# 2018-12-17_02-16-071.net
KiCad netlist of a schematic drawn in Altium Designer
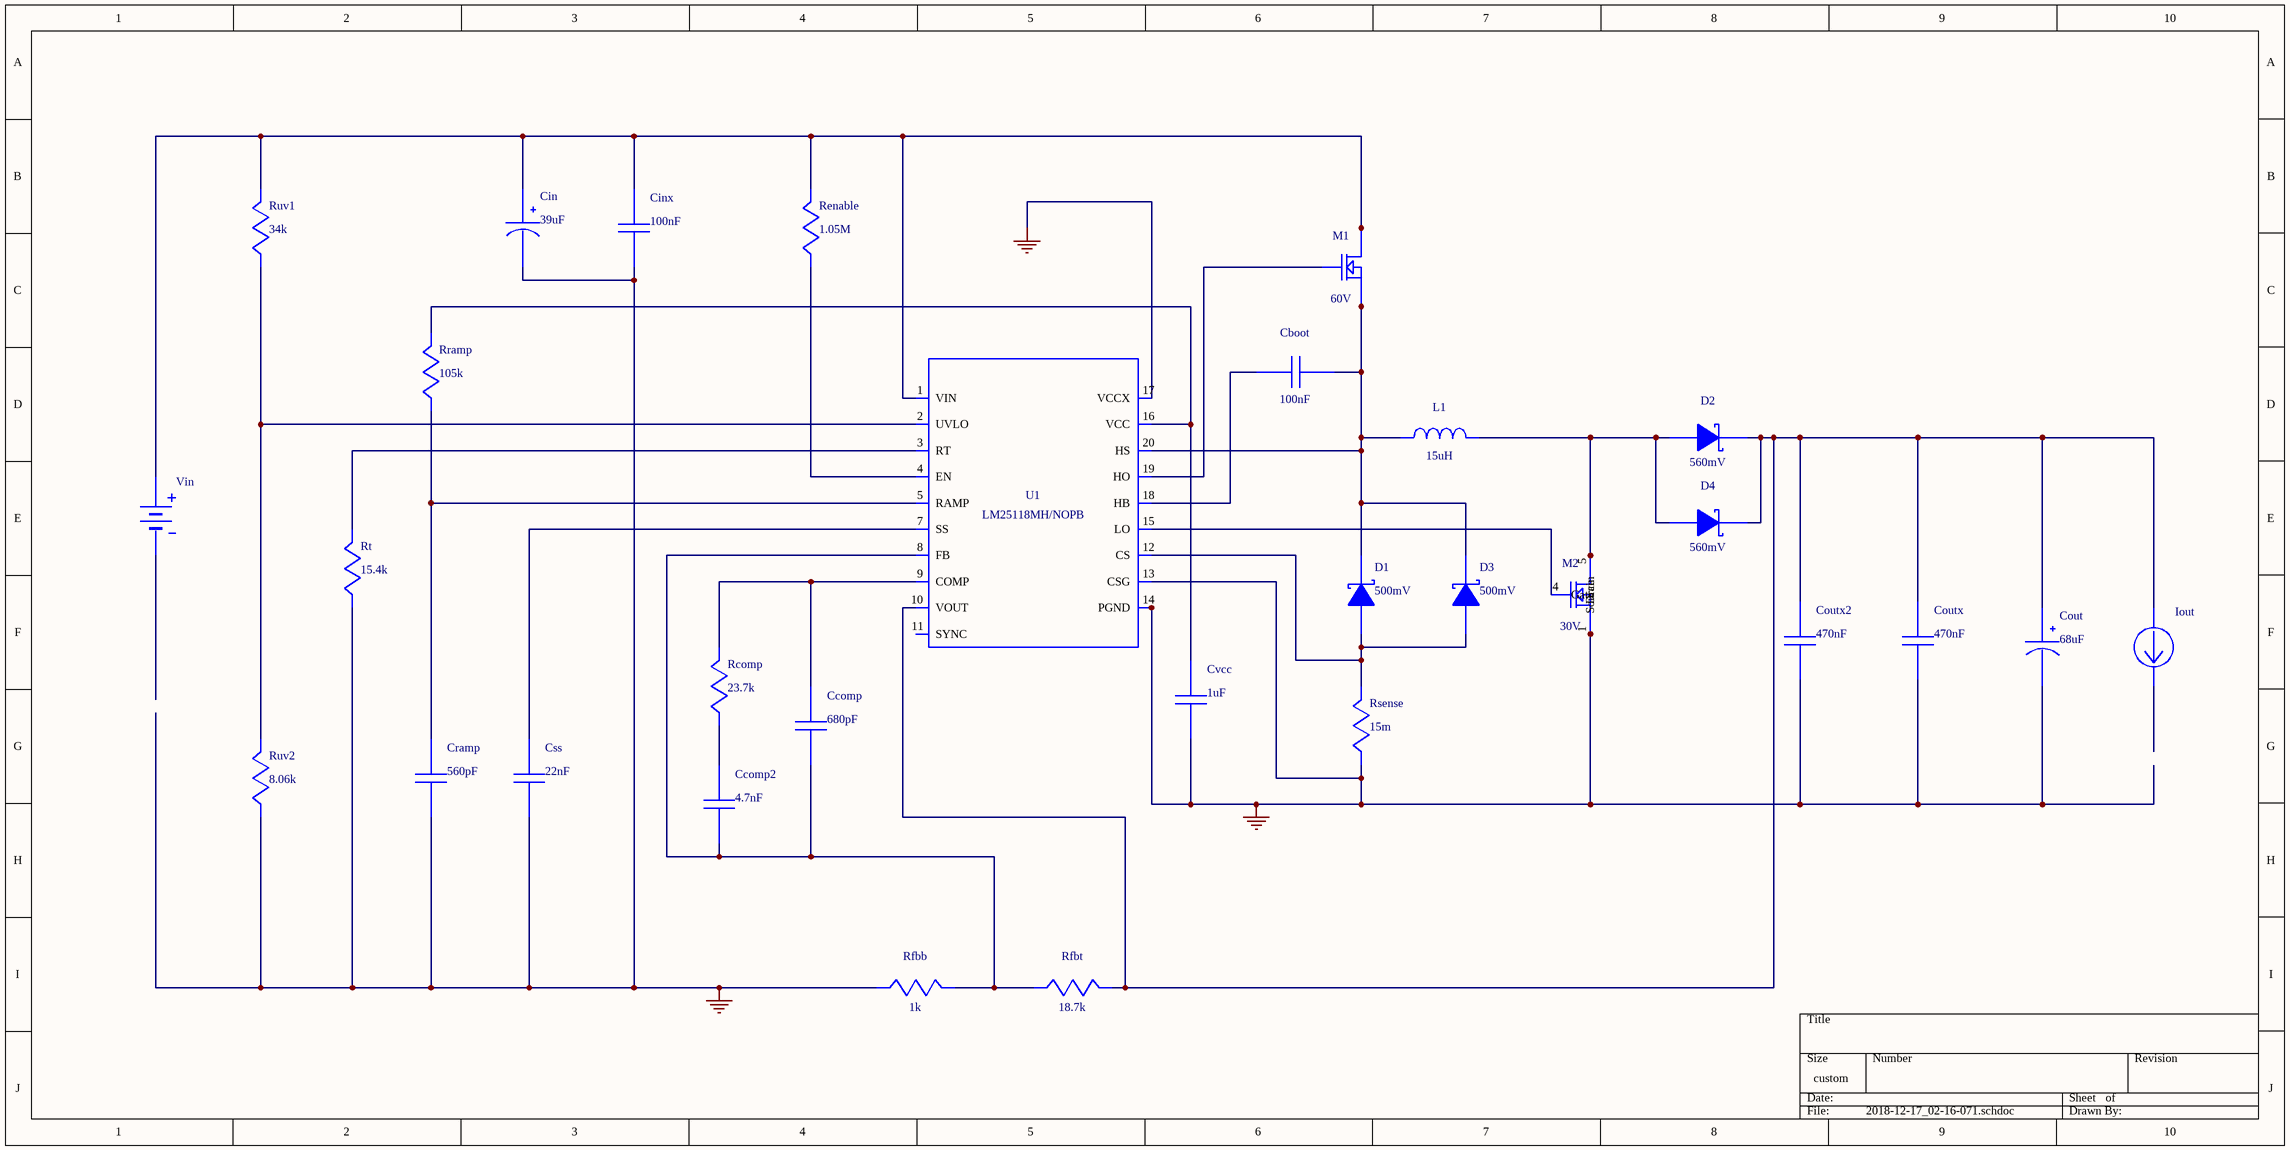
[diagram p0: 2018-12-17_02-16-071.schdoc]

(export (version "E")
  (design (tool "Eeschema 10.0.6"))
  (components
    (comp (ref "Cboot")
      (value "100nF")
      (description "08053C104JAZ2A")
      (libsource (lib "TI WEBENCH") (part "Cboot"))
    )
    (comp (ref "Ccomp")
      (value "680pF")
      (description "CGA2B2C0G1H681J0")
      (fields (field (name "MANUFACTURER PART NUMBER") "CGA2B2C0G1H681J050BA"))
      (libsource (lib "TI WEBENCH") (part "Ccomp"))
    )
    (comp (ref "Ccomp2")
      (value "4.7nF")
      (description "CGA4C2C0G1H472J0")
      (fields (field (name "MANUFACTURER PART NUMBER") "CGA4C2C0G1H472J060AA"))
      (libsource (lib "TI WEBENCH") (part "Ccomp2"))
    )
    (comp (ref "Cin") (value "39uF") (description "50SVPF39M") (libsource (lib "TI WEBENCH") (part "Cin")))
    (comp (ref "Cinx")
      (value "100nF")
      (description "C1005X7R1H104K05")
      (fields (field (name "MANUFACTURER PART NUMBER") "C1005X7R1H104K050BB"))
      (libsource (lib "TI WEBENCH") (part "Cinx"))
    )
    (comp (ref "Cout") (value "68uF") (description "50SVPF68M") (libsource (lib "TI WEBENCH") (part "Cout")))
    (comp (ref "Coutx")
      (value "470nF")
      (description "C1608X7R1H474K08")
      (fields (field (name "MANUFACTURER PART NUMBER") "C1608X7R1H474K080AC"))
      (libsource (lib "TI WEBENCH") (part "Coutx"))
    )
    (comp (ref "Coutx2")
      (value "470nF")
      (description "C1608X7R1H474K08")
      (fields (field (name "MANUFACTURER PART NUMBER") "C1608X7R1H474K080AC"))
      (libsource (lib "TI WEBENCH") (part "Coutx2"))
    )
    (comp (ref "Cramp")
      (value "560pF")
      (description "GRM1555C1H561JA0")
      (fields (field (name "MANUFACTURER PART NUMBER") "GRM1555C1H561JA01J"))
      (libsource (lib "TI WEBENCH") (part "Cramp"))
    )
    (comp (ref "Css")
      (value "22nF")
      (description "CGA4J2C0G1H223J1")
      (fields (field (name "MANUFACTURER PART NUMBER") "CGA4J2C0G1H223J125AA"))
      (libsource (lib "TI WEBENCH") (part "Css"))
    )
    (comp (ref "Cvcc")
      (value "1uF")
      (description "C1608X5R1H105K08")
      (fields (field (name "MANUFACTURER PART NUMBER") "C1608X5R1H105K080AB"))
      (libsource (lib "TI WEBENCH") (part "Cvcc"))
    )
    (comp (ref "D1") (value "500mV") (description "B340A-13-F") (libsource (lib "TI WEBENCH") (part "D1")))
    (comp (ref "D2") (value "560mV") (description "PDS760-13") (libsource (lib "TI WEBENCH") (part "D2")))
    (comp (ref "D3") (value "500mV") (description "B340A-13-F") (libsource (lib "TI WEBENCH") (part "D3")))
    (comp (ref "D4") (value "560mV") (description "PDS760-13") (libsource (lib "TI WEBENCH") (part "D4")))
    (comp (ref "Iout") (value "WB_CURRENT_LOAD") (libsource (lib "TI WEBENCH") (part "Iout")))
    (comp (ref "L1") (value "15uH") (description "XAL1010-153MEB") (libsource (lib "TI WEBENCH") (part "L1")))
    (comp (ref "M1") (value "60V") (description "BSZ100N06LS3 G") (libsource (lib "TI WEBENCH") (part "M1")))
    (comp (ref "M2") (value "30V") (description "CSD17308Q3") (libsource (lib "TI WEBENCH") (part "M2")))
    (comp (ref "Rcomp")
      (value "23.7k")
      (description "RC0201FR-0723K7L")
      (libsource (lib "TI WEBENCH") (part "Rcomp"))
    )
    (comp (ref "Renable")
      (value "1.05M")
      (description "CRCW04021M05FKED")
      (libsource (lib "TI WEBENCH") (part "Renable"))
    )
    (comp (ref "Rfbb")
      (value "1k")
      (description "ERJ-6ENF1001V")
      (libsource (lib "TI WEBENCH") (part "Rfbb"))
    )
    (comp (ref "Rfbt")
      (value "18.7k")
      (description "RC0201FR-0718K7L")
      (libsource (lib "TI WEBENCH") (part "Rfbt"))
    )
    (comp (ref "Rramp")
      (value "105k")
      (description "RC0201FR-07105KL")
      (libsource (lib "TI WEBENCH") (part "Rramp"))
    )
    (comp (ref "Rsense")
      (value "15m")
      (description "PRL1632-R015-F-T")
      (fields (field (name "MANUFACTURER PART NUMBER") "PRL1632-R015-F-T1"))
      (libsource (lib "TI WEBENCH") (part "Rsense"))
    )
    (comp (ref "Rt")
      (value "15.4k")
      (description "RC0201FR-0715K4L")
      (libsource (lib "TI WEBENCH") (part "Rt"))
    )
    (comp (ref "Ruv1")
      (value "34k")
      (description "CRCW040234K0FKED")
      (libsource (lib "TI WEBENCH") (part "Ruv1"))
    )
    (comp (ref "Ruv2")
      (value "8.06k")
      (description "CRCW04028K06FKED")
      (libsource (lib "WBDesign") (part "Ruv2"))
    )
    (comp (ref "U1")
      (value "LM25118MH/NOPB")
      (fields (field (name "PACKAGEREFERENCE") "LM25118MH/NOPB"))
      (libsource (lib "TI WEBENCH") (part "U1"))
    )
    (comp (ref "Vin") (value "WB_BATTERY") (libsource (lib "TI WEBENCH") (part "Vin")))
  )
  (nets
    (net (code "1") (name "0") (class "Default")
      (node (ref "Cin") (pin "2") (pinfunction "-_2") (pintype "passive"))
      (node (ref "Cinx") (pin "2") (pinfunction "2_2") (pintype "passive"))
      (node (ref "Cout") (pin "2") (pinfunction "-_2") (pintype "passive"))
      (node (ref "Coutx") (pin "2") (pinfunction "2_2") (pintype "passive"))
      (node (ref "Coutx2") (pin "2") (pinfunction "2_2") (pintype "passive"))
      (node (ref "Cramp") (pin "2") (pinfunction "2_2") (pintype "passive"))
      (node (ref "Css") (pin "2") (pinfunction "2_2") (pintype "passive"))
      (node (ref "Cvcc") (pin "2") (pinfunction "2_2") (pintype "passive"))
      (node (ref "M2") (pin "1") (pinfunction "Source_1") (pintype "passive"))
      (node (ref "M2") (pin "2") (pinfunction "Source_2") (pintype "passive"))
      (node (ref "M2") (pin "3") (pinfunction "Source_3") (pintype "passive"))
      (node (ref "Rfbb") (pin "2") (pinfunction "2_2") (pintype "passive"))
      (node (ref "Rsense") (pin "2") (pinfunction "2_2") (pintype "passive"))
      (node (ref "Rt") (pin "2") (pinfunction "2_2") (pintype "passive"))
      (node (ref "Ruv2") (pin "2") (pinfunction "2_2") (pintype "passive"))
      (node (ref "U1") (pin "13") (pinfunction "CSG_13") (pintype "passive"))
      (node (ref "U1") (pin "14") (pinfunction "PGND_14") (pintype "passive"))
      (node (ref "U1") (pin "17") (pinfunction "VCCX_17") (pintype "passive"))
      (node (ref "U1") (pin "21") (pinfunction "EXP-PAD_21") (pintype "passive"))
      (node (ref "U1") (pin "6") (pinfunction "AGND_6") (pintype "passive"))
    )
    (net (code "2") (name "Net-(Ccomp2-Pad1)") (class "Default")
      (node (ref "Ccomp2") (pin "1") (pinfunction "1_1") (pintype "passive"))
      (node (ref "Rcomp") (pin "2") (pinfunction "2_2") (pintype "passive"))
    )
    (net (code "3") (name "Net-(Cin-+)") (class "Default")
      (node (ref "Cin") (pin "1") (pinfunction "+_1") (pintype "passive"))
      (node (ref "Cinx") (pin "1") (pinfunction "1_1") (pintype "passive"))
      (node (ref "M1") (pin "5") (pinfunction "Drain_5") (pintype "passive"))
      (node (ref "M1") (pin "6") (pinfunction "Drain_6") (pintype "passive"))
      (node (ref "M1") (pin "7") (pinfunction "Drain_7") (pintype "passive"))
      (node (ref "M1") (pin "8") (pinfunction "Drain_8") (pintype "passive"))
      (node (ref "M1") (pin "9") (pinfunction "Drain_9") (pintype "passive"))
      (node (ref "Renable") (pin "1") (pinfunction "1_1") (pintype "passive"))
      (node (ref "Ruv1") (pin "1") (pinfunction "1_1") (pintype "passive"))
      (node (ref "U1") (pin "1") (pinfunction "VIN_1") (pintype "passive"))
      (node (ref "Vin") (pin "1") (pinfunction "+_1") (pintype "passive"))
    )
    (net (code "4") (name "Net-(Cout-+)") (class "Default")
      (node (ref "Cout") (pin "1") (pinfunction "+_1") (pintype "passive"))
      (node (ref "Coutx") (pin "1") (pinfunction "1_1") (pintype "passive"))
      (node (ref "Coutx2") (pin "1") (pinfunction "1_1") (pintype "passive"))
      (node (ref "D2") (pin "2") (pinfunction "K_2") (pintype "passive"))
      (node (ref "D4") (pin "2") (pinfunction "K_2") (pintype "passive"))
      (node (ref "Iout") (pin "1") (pinfunction "+_1") (pintype "passive"))
      (node (ref "Rfbt") (pin "1") (pinfunction "1_1") (pintype "passive"))
      (node (ref "U1") (pin "10") (pinfunction "VOUT_10") (pintype "passive"))
    )
    (net (code "5") (name "Net-(D1-A)") (class "Default")
      (node (ref "D1") (pin "2") (pinfunction "A_2") (pintype "passive"))
      (node (ref "D3") (pin "2") (pinfunction "A_2") (pintype "passive"))
      (node (ref "Rsense") (pin "1") (pinfunction "1_1") (pintype "passive"))
      (node (ref "U1") (pin "12") (pinfunction "CS_12") (pintype "passive"))
    )
    (net (code "6") (name "Net-(D1-K)") (class "Default")
      (node (ref "Cboot") (pin "1") (pinfunction "1_1") (pintype "passive"))
      (node (ref "D1") (pin "1") (pinfunction "K_1") (pintype "passive"))
      (node (ref "D3") (pin "1") (pinfunction "K_1") (pintype "passive"))
      (node (ref "L1") (pin "2") (pinfunction "2_2") (pintype "passive"))
      (node (ref "M1") (pin "1") (pinfunction "Source_1") (pintype "passive"))
      (node (ref "M1") (pin "2") (pinfunction "Source_2") (pintype "passive"))
      (node (ref "M1") (pin "3") (pinfunction "Source_3") (pintype "passive"))
      (node (ref "U1") (pin "20") (pinfunction "HS_20") (pintype "passive"))
    )
    (net (code "7") (name "Net-(D2-A)") (class "Default")
      (node (ref "D2") (pin "1") (pinfunction "A_1") (pintype "passive"))
      (node (ref "D4") (pin "1") (pinfunction "A_1") (pintype "passive"))
      (node (ref "L1") (pin "1") (pinfunction "1_1") (pintype "passive"))
      (node (ref "M2") (pin "5") (pinfunction "Drain_5") (pintype "passive"))
      (node (ref "M2") (pin "6") (pinfunction "Drain_6") (pintype "passive"))
      (node (ref "M2") (pin "7") (pinfunction "Drain_7") (pintype "passive"))
      (node (ref "M2") (pin "8") (pinfunction "Drain_8") (pintype "passive"))
      (node (ref "M2") (pin "9") (pinfunction "Drain_9") (pintype "passive"))
    )
    (net (code "8") (name "Net-(M1-Gate)") (class "Default")
      (node (ref "M1") (pin "4") (pinfunction "Gate_4") (pintype "passive"))
      (node (ref "U1") (pin "19") (pinfunction "HO_19") (pintype "passive"))
    )
    (net (code "9") (name "Net-(M2-Gate)") (class "Default")
      (node (ref "M2") (pin "4") (pinfunction "Gate_4") (pintype "passive"))
      (node (ref "U1") (pin "15") (pinfunction "LO_15") (pintype "passive"))
    )
    (net (code "10") (name "Net-(U1-COMP)") (class "Default")
      (node (ref "Ccomp") (pin "1") (pinfunction "1_1") (pintype "passive"))
      (node (ref "Rcomp") (pin "1") (pinfunction "1_1") (pintype "passive"))
      (node (ref "U1") (pin "9") (pinfunction "COMP_9") (pintype "passive"))
    )
    (net (code "11") (name "Net-(U1-EN)") (class "Default")
      (node (ref "Renable") (pin "2") (pinfunction "2_2") (pintype "passive"))
      (node (ref "U1") (pin "4") (pinfunction "EN_4") (pintype "passive"))
    )
    (net (code "12") (name "Net-(U1-FB)") (class "Default")
      (node (ref "Ccomp") (pin "2") (pinfunction "2_2") (pintype "passive"))
      (node (ref "Ccomp2") (pin "2") (pinfunction "2_2") (pintype "passive"))
      (node (ref "Rfbb") (pin "1") (pinfunction "1_1") (pintype "passive"))
      (node (ref "Rfbt") (pin "2") (pinfunction "2_2") (pintype "passive"))
      (node (ref "U1") (pin "8") (pinfunction "FB_8") (pintype "passive"))
    )
    (net (code "13") (name "Net-(U1-HB)") (class "Default")
      (node (ref "Cboot") (pin "2") (pinfunction "2_2") (pintype "passive"))
      (node (ref "U1") (pin "18") (pinfunction "HB_18") (pintype "passive"))
    )
    (net (code "14") (name "Net-(U1-RAMP)") (class "Default")
      (node (ref "Cramp") (pin "1") (pinfunction "1_1") (pintype "passive"))
      (node (ref "Rramp") (pin "2") (pinfunction "2_2") (pintype "passive"))
      (node (ref "U1") (pin "5") (pinfunction "RAMP_5") (pintype "passive"))
    )
    (net (code "15") (name "Net-(U1-RT)") (class "Default")
      (node (ref "Rt") (pin "1") (pinfunction "1_1") (pintype "passive"))
      (node (ref "U1") (pin "3") (pinfunction "RT_3") (pintype "passive"))
    )
    (net (code "16") (name "Net-(U1-SS)") (class "Default")
      (node (ref "Css") (pin "1") (pinfunction "1_1") (pintype "passive"))
      (node (ref "U1") (pin "7") (pinfunction "SS_7") (pintype "passive"))
    )
    (net (code "17") (name "Net-(U1-UVLO)") (class "Default")
      (node (ref "Ruv1") (pin "2") (pinfunction "2_2") (pintype "passive"))
      (node (ref "Ruv2") (pin "1") (pinfunction "1_1") (pintype "passive"))
      (node (ref "U1") (pin "2") (pinfunction "UVLO_2") (pintype "passive"))
    )
    (net (code "18") (name "Net-(U1-VCC)") (class "Default")
      (node (ref "Cvcc") (pin "1") (pinfunction "1_1") (pintype "passive"))
      (node (ref "Rramp") (pin "1") (pinfunction "1_1") (pintype "passive"))
      (node (ref "U1") (pin "16") (pinfunction "VCC_16") (pintype "passive"))
    )
    (net (code "19") (name "unconnected-(Iout---Pad2)") (class "Default")
      (node (ref "Iout") (pin "2") (pinfunction "-_2") (pintype "passive"))
    )
    (net (code "20") (name "unconnected-(U1-SYNC-Pad11)") (class "Default")
      (node (ref "U1") (pin "11") (pinfunction "SYNC_11") (pintype "passive"))
    )
    (net (code "21") (name "unconnected-(Vin---Pad2)") (class "Default")
      (node (ref "Vin") (pin "2") (pinfunction "-_2") (pintype "passive"))
    )
  )
)
